# MAX3232.net
KiCad netlist of a schematic drawn in Altium Designer
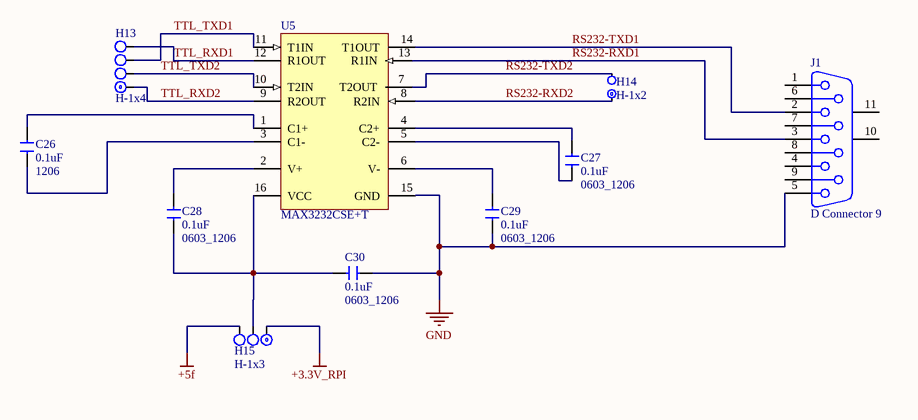
[diagram p0: MAX3232.SchDoc]

(export (version "E")
  (design (tool "Eeschema 10.0.6"))
  (components
    (comp (ref "C26")
      (value "0.1uF")
      (footprint "SMD_CHIP_Cap_Cer_1206")
      (description "SMD_CHIP_CAP_CER_1206")
      (fields (field (name "ALTIUM_VALUE") "1206"))
      (libsource (lib "SMDCapacitors") (part "SMD_CHIP_CAP_CER_1206"))
    )
    (comp (ref "C27")
      (value "0.1uF")
      (footprint "SMD_CHIP_CAP_CER_0603_TO_1206")
      (description "SMD_CHIP_CAP_CER_0603_TO_1206")
      (fields (field (name "ALTIUM_VALUE") "0603_1206"))
      (libsource (lib "SMDCapacitors") (part "SMD_CHIP_CAP_CER_0603_TO_1206"))
    )
    (comp (ref "C28")
      (value "0.1uF")
      (footprint "SMD_CHIP_CAP_CER_0603_TO_1206")
      (description "SMD_CHIP_CAP_CER_0603_TO_1206")
      (fields (field (name "ALTIUM_VALUE") "0603_1206"))
      (libsource (lib "SMDCapacitors") (part "SMD_CHIP_CAP_CER_0603_TO_1206"))
    )
    (comp (ref "C29")
      (value "0.1uF")
      (footprint "SMD_CHIP_CAP_CER_0603_TO_1206")
      (description "SMD_CHIP_CAP_CER_0603_TO_1206")
      (fields (field (name "ALTIUM_VALUE") "0603_1206"))
      (libsource (lib "SMDCapacitors") (part "SMD_CHIP_CAP_CER_0603_TO_1206"))
    )
    (comp (ref "C30")
      (value "0.1uF")
      (footprint "SMD_CHIP_CAP_CER_0603_TO_1206")
      (description "SMD_CHIP_CAP_CER_0603_TO_1206")
      (fields (field (name "ALTIUM_VALUE") "0603_1206"))
      (libsource (lib "SMDCapacitors") (part "SMD_CHIP_CAP_CER_0603_TO_1206"))
    )
    (comp (ref "H13") (value "H-1x4") (footprint "J1x4") (libsource (lib "Connektor") (part "H-1x4")))
    (comp (ref "H14") (value "H-1x2") (footprint "J1x2") (libsource (lib "Connektor") (part "H-1x2")))
    (comp (ref "H15") (value "H-1x3") (footprint "J1x3") (libsource (lib "Connektor") (part "H-1x3")))
    (comp (ref "J1")
      (value "D Connector 9")
      (footprint "DB9-HEMBRA")
      (description "Receptacle Assembly, 9 Position, Right Angle")
      (fields (field (name "PUBLISHER") "Altium Limited"))
      (libsource (lib "PCBConnectors") (part "D Connector 9"))
    )
    (comp (ref "U5")
      (value "MAX3232CSE+T")
      (footprint "MAXM-S16+1_M")
      (fields (field (name "MANUFACTURER") "MaximIntegrated"))
      (libsource (lib "Altium Content Vault") (part "MAXM-MAX3232CSE+T-SOIC-16"))
    )
  )
  (nets
    (net (code "1") (name "+3.3V_RPI") (class "Default")
      (node (ref "H15") (pin "1") (pinfunction "1_1") (pintype "passive"))
    )
    (net (code "2") (name "+5f") (class "Default")
      (node (ref "H15") (pin "3") (pinfunction "3_3") (pintype "passive"))
    )
    (net (code "3") (name "/RS232-RXD1") (class "Default")
      (node (ref "J1") (pin "3") (pinfunction "3_3") (pintype "passive"))
      (node (ref "U5") (pin "13") (pinfunction "R1IN_13") (pintype "input"))
    )
    (net (code "4") (name "/RS232-RXD2") (class "Default")
      (node (ref "H14") (pin "1") (pinfunction "1_1") (pintype "passive"))
      (node (ref "U5") (pin "8") (pinfunction "R2IN_8") (pintype "input"))
    )
    (net (code "5") (name "/RS232-TXD1") (class "Default")
      (node (ref "J1") (pin "2") (pinfunction "2_2") (pintype "passive"))
      (node (ref "U5") (pin "14") (pinfunction "T1OUT_14") (pintype "tri_state"))
    )
    (net (code "6") (name "/RS232-TXD2") (class "Default")
      (node (ref "H14") (pin "2") (pinfunction "2_2") (pintype "passive"))
      (node (ref "U5") (pin "7") (pinfunction "T2OUT_7") (pintype "tri_state"))
    )
    (net (code "7") (name "/TTL_RXD1") (class "Default")
      (node (ref "H13") (pin "4") (pinfunction "4_4") (pintype "passive"))
      (node (ref "U5") (pin "12") (pinfunction "R1OUT_12") (pintype "tri_state"))
    )
    (net (code "8") (name "/TTL_RXD2") (class "Default")
      (node (ref "H13") (pin "1") (pinfunction "1_1") (pintype "passive"))
      (node (ref "U5") (pin "9") (pinfunction "R2OUT_9") (pintype "tri_state"))
    )
    (net (code "9") (name "/TTL_TXD1") (class "Default")
      (node (ref "H13") (pin "3") (pinfunction "3_3") (pintype "passive"))
      (node (ref "U5") (pin "11") (pinfunction "T1IN_11") (pintype "input"))
    )
    (net (code "10") (name "/TTL_TXD2") (class "Default")
      (node (ref "H13") (pin "2") (pinfunction "2_2") (pintype "passive"))
      (node (ref "U5") (pin "10") (pinfunction "T2IN_10") (pintype "input"))
    )
    (net (code "11") (name "GND") (class "Default")
      (node (ref "C29") (pin "2") (pinfunction "2_2") (pintype "passive"))
      (node (ref "C30") (pin "2") (pinfunction "2_2") (pintype "passive"))
      (node (ref "J1") (pin "5") (pinfunction "5_5") (pintype "passive"))
      (node (ref "U5") (pin "15") (pinfunction "GND_15") (pintype "power_in"))
    )
    (net (code "12") (name "Net-(U5-C1+)") (class "Default")
      (node (ref "C26") (pin "1") (pinfunction "1_1") (pintype "passive"))
      (node (ref "U5") (pin "1") (pinfunction "C1+_1") (pintype "passive"))
    )
    (net (code "13") (name "Net-(U5-C1-)") (class "Default")
      (node (ref "C26") (pin "2") (pinfunction "2_2") (pintype "passive"))
      (node (ref "U5") (pin "3") (pinfunction "C1-_3") (pintype "passive"))
    )
    (net (code "14") (name "Net-(U5-C2+)") (class "Default")
      (node (ref "C27") (pin "1") (pinfunction "1_1") (pintype "passive"))
      (node (ref "U5") (pin "4") (pinfunction "C2+_4") (pintype "passive"))
    )
    (net (code "15") (name "Net-(U5-C2-)") (class "Default")
      (node (ref "C27") (pin "2") (pinfunction "2_2") (pintype "passive"))
      (node (ref "U5") (pin "5") (pinfunction "C2-_5") (pintype "passive"))
    )
    (net (code "16") (name "Net-(U5-V+)") (class "Default")
      (node (ref "C28") (pin "1") (pinfunction "1_1") (pintype "passive"))
      (node (ref "U5") (pin "2") (pinfunction "V+_2") (pintype "power_in"))
    )
    (net (code "17") (name "Net-(U5-V-)") (class "Default")
      (node (ref "C29") (pin "1") (pinfunction "1_1") (pintype "passive"))
      (node (ref "U5") (pin "6") (pinfunction "V-_6") (pintype "power_in"))
    )
    (net (code "18") (name "Net-(U5-VCC)") (class "Default")
      (node (ref "C28") (pin "2") (pinfunction "2_2") (pintype "passive"))
      (node (ref "C30") (pin "1") (pinfunction "1_1") (pintype "passive"))
      (node (ref "H15") (pin "2") (pinfunction "2_2") (pintype "passive"))
      (node (ref "U5") (pin "16") (pinfunction "VCC_16") (pintype "power_in"))
    )
    (net (code "19") (name "unconnected-(J1-MH1-Pad10)") (class "Default")
      (node (ref "J1") (pin "10") (pinfunction "MH1_10") (pintype "passive"))
    )
    (net (code "20") (name "unconnected-(J1-MH2-Pad11)") (class "Default")
      (node (ref "J1") (pin "11") (pinfunction "MH2_11") (pintype "passive"))
    )
    (net (code "21") (name "unconnected-(J1-Pad1)") (class "Default")
      (node (ref "J1") (pin "1") (pinfunction "1_1") (pintype "passive"))
    )
    (net (code "22") (name "unconnected-(J1-Pad4)") (class "Default")
      (node (ref "J1") (pin "4") (pinfunction "4_4") (pintype "passive"))
    )
    (net (code "23") (name "unconnected-(J1-Pad6)") (class "Default")
      (node (ref "J1") (pin "6") (pinfunction "6_6") (pintype "passive"))
    )
    (net (code "24") (name "unconnected-(J1-Pad7)") (class "Default")
      (node (ref "J1") (pin "7") (pinfunction "7_7") (pintype "passive"))
    )
    (net (code "25") (name "unconnected-(J1-Pad8)") (class "Default")
      (node (ref "J1") (pin "8") (pinfunction "8_8") (pintype "passive"))
    )
    (net (code "26") (name "unconnected-(J1-Pad9)") (class "Default")
      (node (ref "J1") (pin "9") (pinfunction "9_9") (pintype "passive"))
    )
  )
)
